# VFDClock.net
KiCad netlist of a schematic drawn in EAGLE
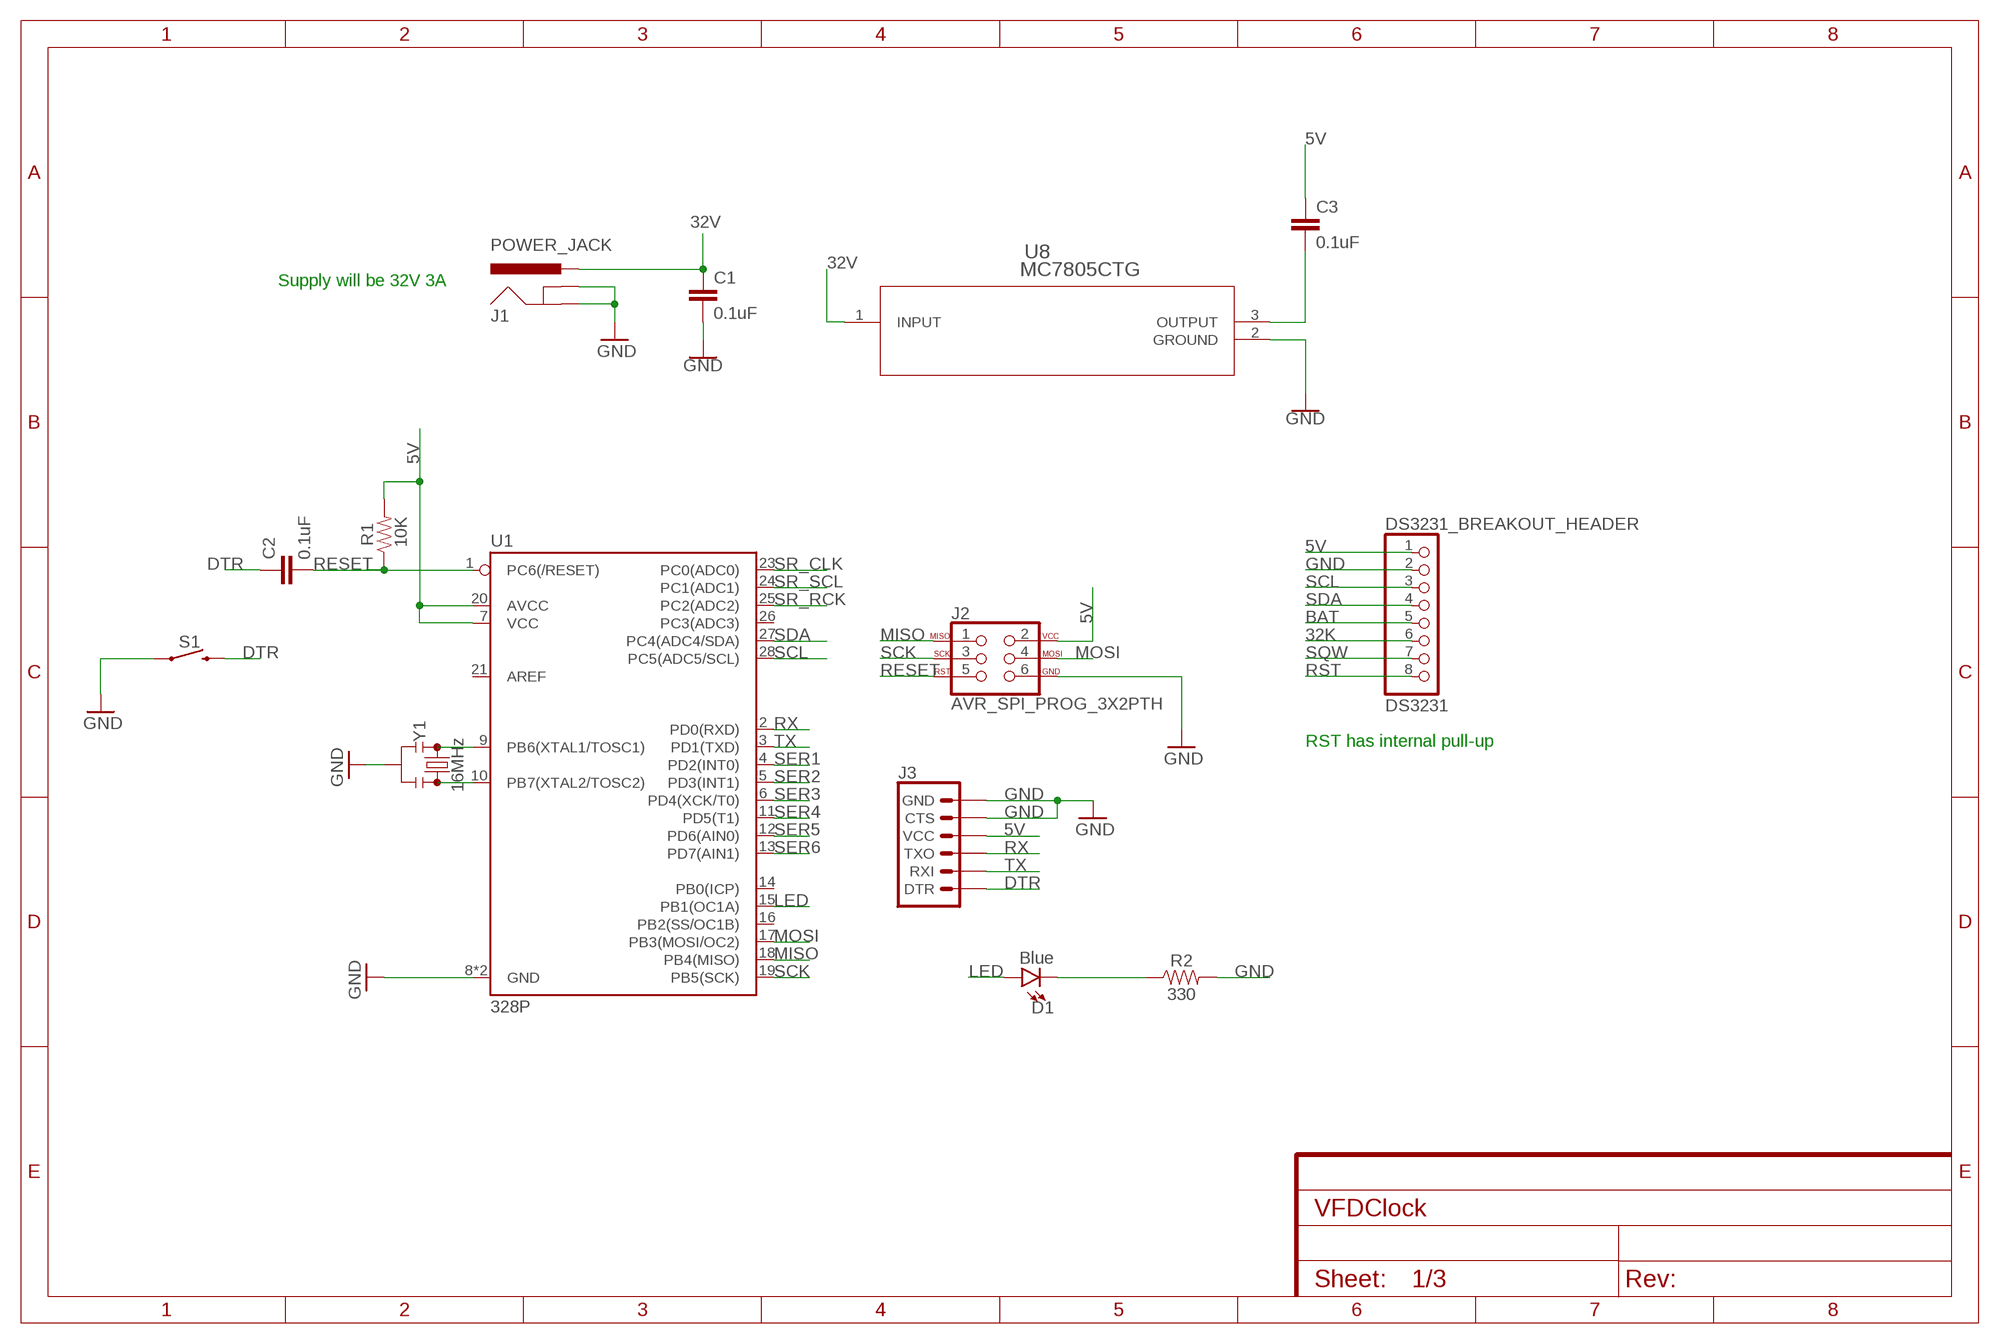
[diagram p0: schematic, sheet 1]
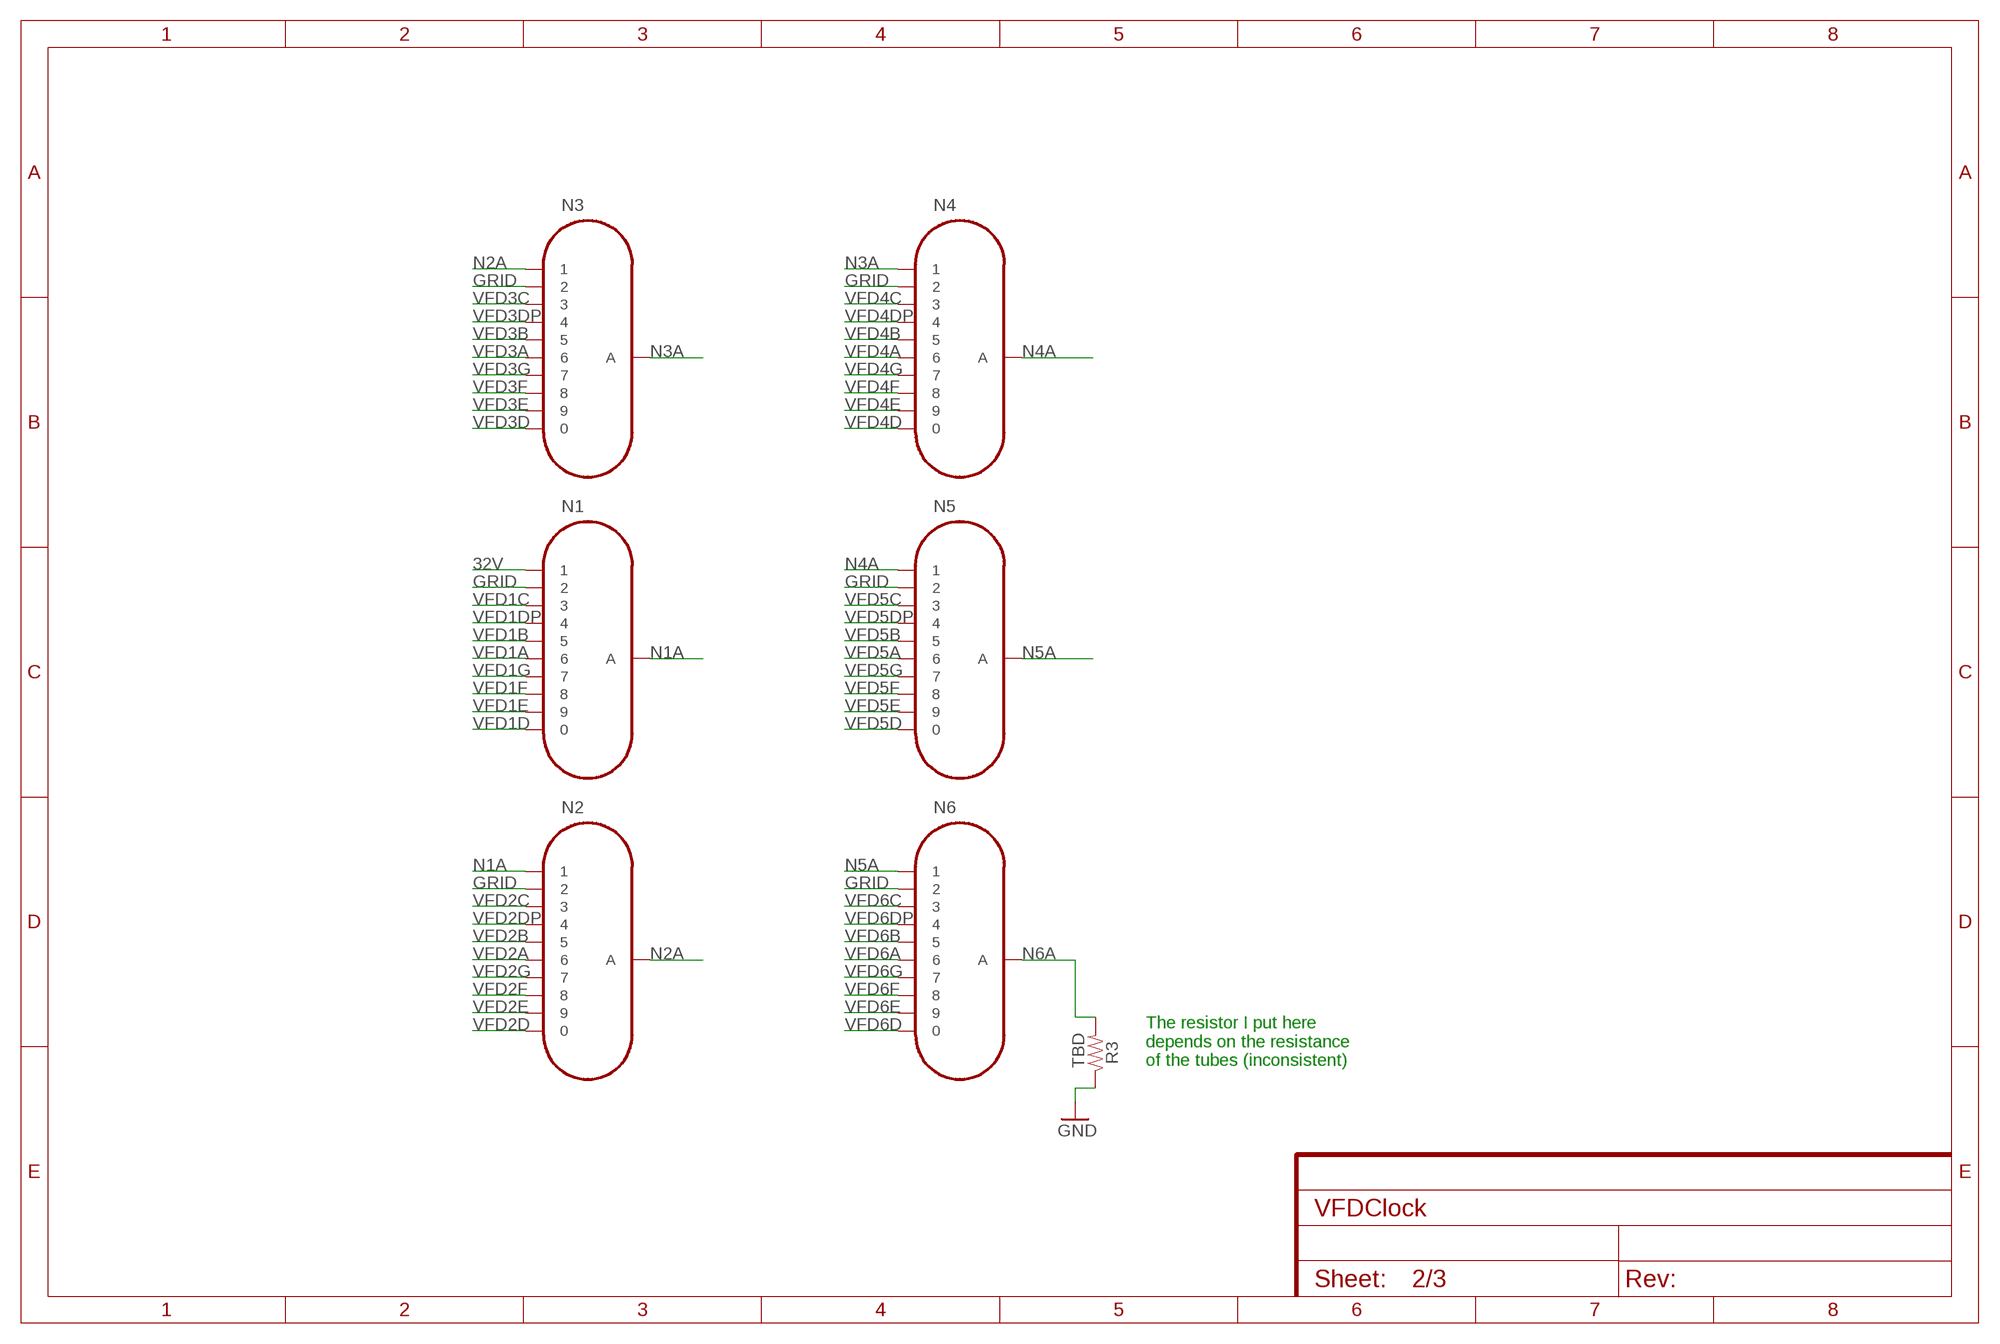
[diagram p1: schematic, sheet 2]
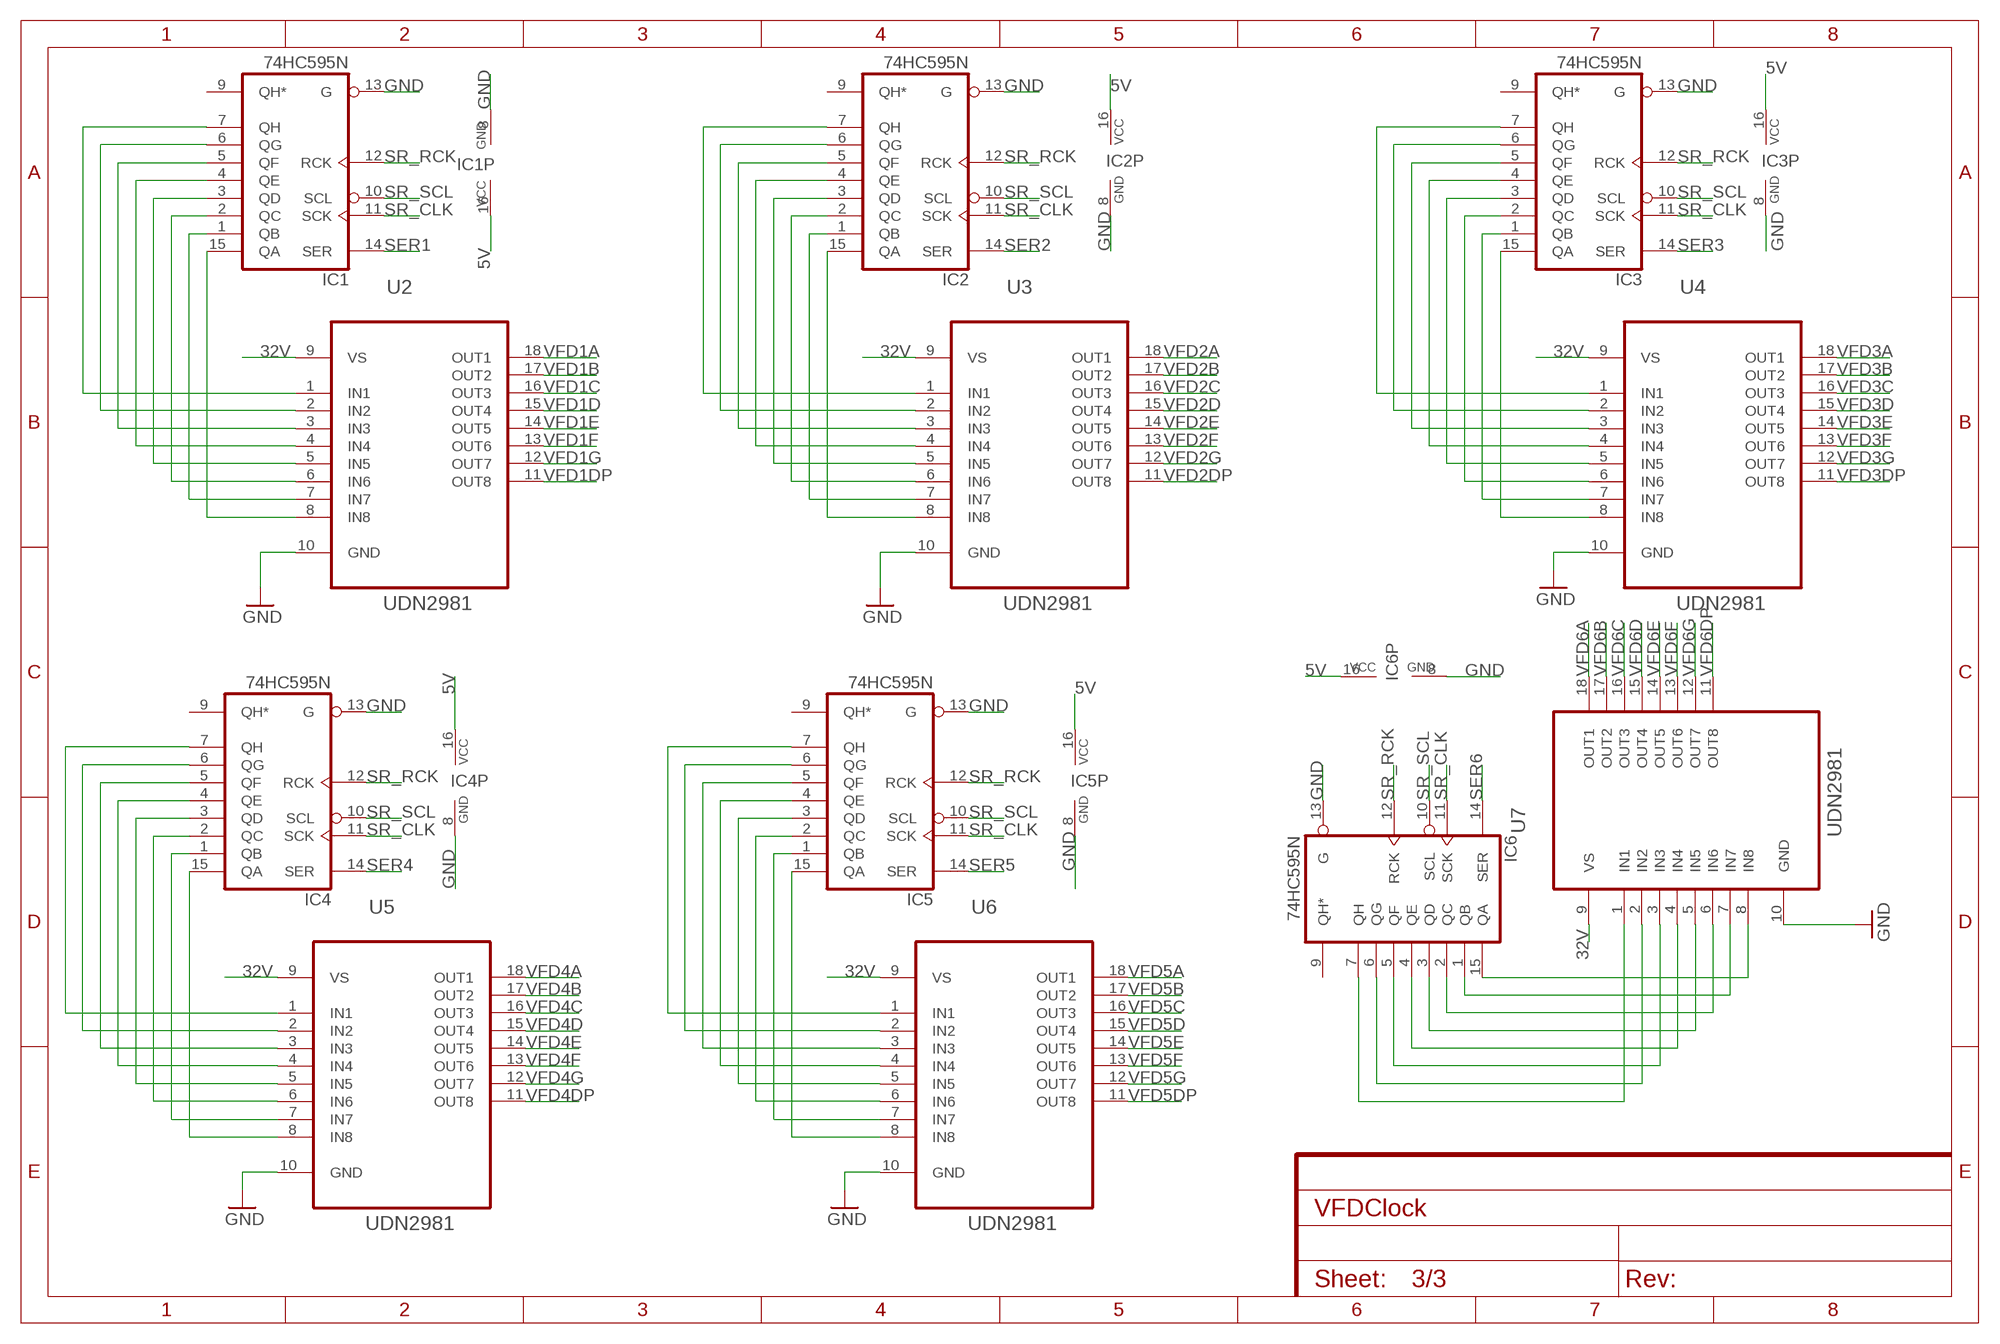
[diagram p2: schematic, sheet 3]

(export (version "E")
  (design (tool "Eeschema 10.0.6"))
  (components
    (comp (ref "C1")
      (value "0.1uF")
      (footprint "eagle-import:CAP-PTH-SMALL-KIT")
      (libsource (lib "eagle-import") (part "0.1UF-KIT-EZ-50V-20%"))
    )
    (comp (ref "C2")
      (value "0.1uF")
      (footprint "eagle-import:CAP-PTH-SMALL-KIT")
      (libsource (lib "eagle-import") (part "0.1UF-KIT-EZ-50V-20%"))
    )
    (comp (ref "C3")
      (value "0.1uF")
      (footprint "eagle-import:0402-CAP")
      (libsource (lib "eagle-import") (part ".1UF-CER"))
    )
    (comp (ref "D1")
      (value "Blue")
      (footprint "eagle-import:LED_5MM")
      (libsource (lib "eagle-import") (part "LED5MM"))
    )
    (comp (ref "DS3231_BREAKOUT_HEADER")
      (value "DS3231")
      (footprint "eagle-import:1X08_ROUND_70")
      (libsource (lib "eagle-import") (part "HEADER-1X870MIL"))
    )
    (comp (ref "J1")
      (value "POWER_JACK")
      (footprint "eagle-import:POWER_JACK_PTH")
      (libsource (lib "eagle-import") (part "POWER_JACK"))
    )
    (comp (ref "J2")
      (value "AVR_SPI_PROG_3X2PTH")
      (footprint "eagle-import:2X3")
      (libsource (lib "eagle-import") (part "AVR_SPI_PROG_3X2PTH"))
    )
    (comp (ref "J3")
      (value "6_PIN_SERIAL_TARGETLONGPADS")
      (footprint "eagle-import:1X06_LONGPADS")
      (libsource (lib "eagle-import") (part "6_PIN_SERIAL_TARGETLONGPADS"))
    )
    (comp (ref "R1")
      (value "10K")
      (footprint "eagle-import:AXIAL-0.3")
      (libsource (lib "eagle-import") (part "RESISTORAXIAL-0.3"))
    )
    (comp (ref "R2")
      (value "330")
      (footprint "eagle-import:AXIAL-0.3")
      (libsource (lib "eagle-import") (part "330OHM-HORIZ-1/10W-5%"))
    )
    (comp (ref "S1")
      (value "MOMENTARY-SWITCH-SPST-PTH-6.0MM")
      (footprint "eagle-import:TACTILE_SWITCH_PTH_6.0MM")
      (libsource (lib "eagle-import") (part "MOMENTARY-SWITCH-SPST-PTH-6.0MM"))
    )
    (comp (ref "U1")
      (value "328P")
      (footprint "eagle-import:DIP28")
      (libsource (lib "eagle-import") (part "ATMEGA328P_PDIP"))
    )
    (comp (ref "U8")
      (value "MC7805CTG")
      (footprint "eagle-import:TO-220AB")
      (libsource (lib "eagle-import") (part "MC7805CTG"))
    )
    (comp (ref "Y1")
      (value "16MHz")
      (footprint "eagle-import:RESONATOR-PTH-7.6X3.8")
      (libsource (lib "eagle-import") (part "RESONATORPTH-7.6X3.8"))
    )
    (comp (ref "N1")
      (value "IN-8")
      (footprint "eagle-import:IN-8")
      (libsource (lib "eagle-import") (part "IN-8"))
    )
    (comp (ref "N2")
      (value "IN-8")
      (footprint "eagle-import:IN-8")
      (libsource (lib "eagle-import") (part "IN-8"))
    )
    (comp (ref "N3")
      (value "IN-8")
      (footprint "eagle-import:IN-8")
      (libsource (lib "eagle-import") (part "IN-8"))
    )
    (comp (ref "N4")
      (value "IN-8")
      (footprint "eagle-import:IN-8")
      (libsource (lib "eagle-import") (part "IN-8"))
    )
    (comp (ref "N5")
      (value "IN-8")
      (footprint "eagle-import:IN-8")
      (libsource (lib "eagle-import") (part "IN-8"))
    )
    (comp (ref "N6")
      (value "IN-8")
      (footprint "eagle-import:IN-8")
      (libsource (lib "eagle-import") (part "IN-8"))
    )
    (comp (ref "R3")
      (value "TBD")
      (footprint "eagle-import:AXIAL-0.3")
      (libsource (lib "eagle-import") (part "RESISTORAXIAL-0.3"))
    )
    (comp (ref "IC1")
      (value "74HC595N")
      (footprint "eagle-import:DIL16")
      (libsource (lib "eagle-import") (part "74595NHC"))
    )
    (comp (ref "IC2")
      (value "74HC595N")
      (footprint "eagle-import:DIL16")
      (libsource (lib "eagle-import") (part "74595NHC"))
    )
    (comp (ref "IC3")
      (value "74HC595N")
      (footprint "eagle-import:DIL16")
      (libsource (lib "eagle-import") (part "74595NHC"))
    )
    (comp (ref "IC4")
      (value "74HC595N")
      (footprint "eagle-import:DIL16")
      (libsource (lib "eagle-import") (part "74595NHC"))
    )
    (comp (ref "IC5")
      (value "74HC595N")
      (footprint "eagle-import:DIL16")
      (libsource (lib "eagle-import") (part "74595NHC"))
    )
    (comp (ref "IC6")
      (value "74HC595N")
      (footprint "eagle-import:DIL16")
      (libsource (lib "eagle-import") (part "74595NHC"))
    )
    (comp (ref "U2")
      (value "UDN2981")
      (footprint "eagle-import:DIP254P762X533-18")
      (fields (field (name "MF") "Allegro MicroSystems LLC"))
      (libsource (lib "eagle-import") (part "UDN2981"))
    )
    (comp (ref "U3")
      (value "UDN2981")
      (footprint "eagle-import:DIP254P762X533-18")
      (fields (field (name "MF") "Allegro MicroSystems LLC"))
      (libsource (lib "eagle-import") (part "UDN2981"))
    )
    (comp (ref "U4")
      (value "UDN2981")
      (footprint "eagle-import:DIP254P762X533-18")
      (fields (field (name "MF") "Allegro MicroSystems LLC"))
      (libsource (lib "eagle-import") (part "UDN2981"))
    )
    (comp (ref "U5")
      (value "UDN2981")
      (footprint "eagle-import:DIP254P762X533-18")
      (fields (field (name "MF") "Allegro MicroSystems LLC"))
      (libsource (lib "eagle-import") (part "UDN2981"))
    )
    (comp (ref "U6")
      (value "UDN2981")
      (footprint "eagle-import:DIP254P762X533-18")
      (fields (field (name "MF") "Allegro MicroSystems LLC"))
      (libsource (lib "eagle-import") (part "UDN2981"))
    )
    (comp (ref "U7")
      (value "UDN2981")
      (footprint "eagle-import:DIP254P762X533-18")
      (fields (field (name "MF") "Allegro MicroSystems LLC"))
      (libsource (lib "eagle-import") (part "UDN2981"))
    )
  )
  (nets
    (net (code "1") (name "5V") (class "Default")
      (node (ref "C3") (pin "1") (pinfunction "1_1") (pintype "passive"))
      (node (ref "DS3231_BREAKOUT_HEADER") (pin "1") (pinfunction "1_1") (pintype "passive"))
      (node (ref "IC1") (pin "16") (pinfunction "VCC_16") (pintype "power_in"))
      (node (ref "IC2") (pin "16") (pinfunction "VCC_16") (pintype "power_in"))
      (node (ref "IC3") (pin "16") (pinfunction "VCC_16") (pintype "power_in"))
      (node (ref "IC4") (pin "16") (pinfunction "VCC_16") (pintype "power_in"))
      (node (ref "IC5") (pin "16") (pinfunction "VCC_16") (pintype "power_in"))
      (node (ref "IC6") (pin "16") (pinfunction "VCC_16") (pintype "power_in"))
      (node (ref "J2") (pin "2") (pinfunction "2_2") (pintype "passive"))
      (node (ref "J3") (pin "4") (pinfunction "VCC_4") (pintype "passive"))
      (node (ref "R1") (pin "P$2") (pinfunction "2_P$2") (pintype "passive"))
      (node (ref "U1") (pin "20") (pinfunction "AVCC_20") (pintype "bidirectional"))
      (node (ref "U1") (pin "7") (pinfunction "VCC_7") (pintype "bidirectional"))
    )
    (net (code "2") (name "32K") (class "Default")
      (node (ref "DS3231_BREAKOUT_HEADER") (pin "6") (pinfunction "6_6") (pintype "passive"))
    )
    (net (code "3") (name "32V") (class "Default")
      (node (ref "C1") (pin "1") (pinfunction "1_1") (pintype "passive"))
      (node (ref "J1") (pin "PWR") (pinfunction "PWR_PWR") (pintype "bidirectional"))
      (node (ref "N1") (pin "1") (pinfunction "1_1") (pintype "bidirectional"))
      (node (ref "U2") (pin "9") (pinfunction "VS_9") (pintype "power_in"))
      (node (ref "U3") (pin "9") (pinfunction "VS_9") (pintype "power_in"))
      (node (ref "U4") (pin "9") (pinfunction "VS_9") (pintype "power_in"))
      (node (ref "U5") (pin "9") (pinfunction "VS_9") (pintype "power_in"))
      (node (ref "U6") (pin "9") (pinfunction "VS_9") (pintype "power_in"))
      (node (ref "U7") (pin "9") (pinfunction "VS_9") (pintype "power_in"))
      (node (ref "U8") (pin "1") (pinfunction "INPUT_1") (pintype "input"))
    )
    (net (code "4") (name "BAT") (class "Default")
      (node (ref "DS3231_BREAKOUT_HEADER") (pin "5") (pinfunction "5_5") (pintype "passive"))
    )
    (net (code "5") (name "DTR") (class "Default")
      (node (ref "C2") (pin "1") (pinfunction "1_1") (pintype "passive"))
      (node (ref "J3") (pin "1") (pinfunction "DTR_1") (pintype "passive"))
      (node (ref "S1") (pin "3") (pinfunction "2_3") (pintype "passive"))
    )
    (net (code "6") (name "GND") (class "Default")
      (node (ref "C1") (pin "2") (pinfunction "2_2") (pintype "passive"))
      (node (ref "DS3231_BREAKOUT_HEADER") (pin "2") (pinfunction "2_2") (pintype "passive"))
      (node (ref "IC1") (pin "13") (pinfunction "G_13") (pintype "input"))
      (node (ref "IC1") (pin "8") (pinfunction "GND_8") (pintype "power_in"))
      (node (ref "IC2") (pin "13") (pinfunction "G_13") (pintype "input"))
      (node (ref "IC2") (pin "8") (pinfunction "GND_8") (pintype "power_in"))
      (node (ref "IC3") (pin "13") (pinfunction "G_13") (pintype "input"))
      (node (ref "IC3") (pin "8") (pinfunction "GND_8") (pintype "power_in"))
      (node (ref "IC4") (pin "13") (pinfunction "G_13") (pintype "input"))
      (node (ref "IC4") (pin "8") (pinfunction "GND_8") (pintype "power_in"))
      (node (ref "IC5") (pin "13") (pinfunction "G_13") (pintype "input"))
      (node (ref "IC5") (pin "8") (pinfunction "GND_8") (pintype "power_in"))
      (node (ref "IC6") (pin "13") (pinfunction "G_13") (pintype "input"))
      (node (ref "IC6") (pin "8") (pinfunction "GND_8") (pintype "power_in"))
      (node (ref "J1") (pin "GND") (pinfunction "GND_GND") (pintype "bidirectional"))
      (node (ref "J1") (pin "GNDBREAK") (pinfunction "GNDBREAK_GNDBREAK") (pintype "bidirectional"))
      (node (ref "J2") (pin "6") (pinfunction "6_6") (pintype "passive"))
      (node (ref "J3") (pin "5") (pinfunction "CTS_5") (pintype "passive"))
      (node (ref "J3") (pin "6") (pinfunction "GND_6") (pintype "passive"))
      (node (ref "R2") (pin "P$2") (pinfunction "2_P$2") (pintype "passive"))
      (node (ref "R3") (pin "P$1") (pinfunction "1_P$1") (pintype "passive"))
      (node (ref "S1") (pin "1") (pinfunction "1_1") (pintype "passive"))
      (node (ref "U1") (pin "22") (pinfunction "GND_22") (pintype "bidirectional"))
      (node (ref "U1") (pin "8") (pinfunction "GND_8") (pintype "bidirectional"))
      (node (ref "U2") (pin "10") (pinfunction "GND_10") (pintype "passive"))
      (node (ref "U3") (pin "10") (pinfunction "GND_10") (pintype "passive"))
      (node (ref "U4") (pin "10") (pinfunction "GND_10") (pintype "passive"))
      (node (ref "U5") (pin "10") (pinfunction "GND_10") (pintype "passive"))
      (node (ref "U6") (pin "10") (pinfunction "GND_10") (pintype "passive"))
      (node (ref "U7") (pin "10") (pinfunction "GND_10") (pintype "passive"))
      (node (ref "U8") (pin "2") (pinfunction "GROUND_2") (pintype "power_in"))
      (node (ref "Y1") (pin "2") (pinfunction "2_2") (pintype "passive"))
    )
    (net (code "7") (name "GRID") (class "Default")
      (node (ref "N1") (pin "2") (pinfunction "2_2") (pintype "bidirectional"))
      (node (ref "N2") (pin "2") (pinfunction "2_2") (pintype "bidirectional"))
      (node (ref "N3") (pin "2") (pinfunction "2_2") (pintype "bidirectional"))
      (node (ref "N4") (pin "2") (pinfunction "2_2") (pintype "bidirectional"))
      (node (ref "N5") (pin "2") (pinfunction "2_2") (pintype "bidirectional"))
      (node (ref "N6") (pin "2") (pinfunction "2_2") (pintype "bidirectional"))
    )
    (net (code "8") (name "LED") (class "Default")
      (node (ref "D1") (pin "A") (pinfunction "A_A") (pintype "passive"))
      (node (ref "U1") (pin "15") (pinfunction "PB1(OC1A)_15") (pintype "bidirectional"))
    )
    (net (code "9") (name "MISO") (class "Default")
      (node (ref "J2") (pin "1") (pinfunction "1_1") (pintype "passive"))
      (node (ref "U1") (pin "18") (pinfunction "PB4(MISO)_18") (pintype "bidirectional"))
    )
    (net (code "10") (name "MOSI") (class "Default")
      (node (ref "J2") (pin "4") (pinfunction "4_4") (pintype "passive"))
      (node (ref "U1") (pin "17") (pinfunction "PB3(MOSI/OC2)_17") (pintype "bidirectional"))
    )
    (net (code "11") (name "N1A") (class "Default")
      (node (ref "N1") (pin "A") (pinfunction "A_A") (pintype "bidirectional"))
      (node (ref "N2") (pin "1") (pinfunction "1_1") (pintype "bidirectional"))
    )
    (net (code "12") (name "N2A") (class "Default")
      (node (ref "N2") (pin "A") (pinfunction "A_A") (pintype "bidirectional"))
      (node (ref "N3") (pin "1") (pinfunction "1_1") (pintype "bidirectional"))
    )
    (net (code "13") (name "N3A") (class "Default")
      (node (ref "N3") (pin "A") (pinfunction "A_A") (pintype "bidirectional"))
      (node (ref "N4") (pin "1") (pinfunction "1_1") (pintype "bidirectional"))
    )
    (net (code "14") (name "N4A") (class "Default")
      (node (ref "N4") (pin "A") (pinfunction "A_A") (pintype "bidirectional"))
      (node (ref "N5") (pin "1") (pinfunction "1_1") (pintype "bidirectional"))
    )
    (net (code "15") (name "N5A") (class "Default")
      (node (ref "N5") (pin "A") (pinfunction "A_A") (pintype "bidirectional"))
      (node (ref "N6") (pin "1") (pinfunction "1_1") (pintype "bidirectional"))
    )
    (net (code "16") (name "N6A") (class "Default")
      (node (ref "N6") (pin "A") (pinfunction "A_A") (pintype "bidirectional"))
      (node (ref "R3") (pin "P$2") (pinfunction "2_P$2") (pintype "passive"))
    )
    (net (code "17") (name "Net-(D1-C)") (class "Default")
      (node (ref "D1") (pin "K") (pinfunction "C_K") (pintype "passive"))
      (node (ref "R2") (pin "P$1") (pinfunction "1_P$1") (pintype "passive"))
    )
    (net (code "18") (name "Net-(IC1A-QA)") (class "Default")
      (node (ref "IC1") (pin "15") (pinfunction "QA_15") (pintype "tri_state"))
      (node (ref "U2") (pin "8") (pinfunction "IN8_8") (pintype "input"))
    )
    (net (code "19") (name "Net-(IC1A-QB)") (class "Default")
      (node (ref "IC1") (pin "1") (pinfunction "QB_1") (pintype "tri_state"))
      (node (ref "U2") (pin "7") (pinfunction "IN7_7") (pintype "input"))
    )
    (net (code "20") (name "Net-(IC1A-QC)") (class "Default")
      (node (ref "IC1") (pin "2") (pinfunction "QC_2") (pintype "tri_state"))
      (node (ref "U2") (pin "6") (pinfunction "IN6_6") (pintype "input"))
    )
    (net (code "21") (name "Net-(IC1A-QD)") (class "Default")
      (node (ref "IC1") (pin "3") (pinfunction "QD_3") (pintype "tri_state"))
      (node (ref "U2") (pin "5") (pinfunction "IN5_5") (pintype "input"))
    )
    (net (code "22") (name "Net-(IC1A-QE)") (class "Default")
      (node (ref "IC1") (pin "4") (pinfunction "QE_4") (pintype "tri_state"))
      (node (ref "U2") (pin "4") (pinfunction "IN4_4") (pintype "input"))
    )
    (net (code "23") (name "Net-(IC1A-QF)") (class "Default")
      (node (ref "IC1") (pin "5") (pinfunction "QF_5") (pintype "tri_state"))
      (node (ref "U2") (pin "3") (pinfunction "IN3_3") (pintype "input"))
    )
    (net (code "24") (name "Net-(IC1A-QG)") (class "Default")
      (node (ref "IC1") (pin "6") (pinfunction "QG_6") (pintype "tri_state"))
      (node (ref "U2") (pin "2") (pinfunction "IN2_2") (pintype "input"))
    )
    (net (code "25") (name "Net-(IC1A-QH)") (class "Default")
      (node (ref "IC1") (pin "7") (pinfunction "QH_7") (pintype "tri_state"))
      (node (ref "U2") (pin "1") (pinfunction "IN1_1") (pintype "input"))
    )
    (net (code "26") (name "Net-(IC2A-QA)") (class "Default")
      (node (ref "IC2") (pin "15") (pinfunction "QA_15") (pintype "tri_state"))
      (node (ref "U3") (pin "8") (pinfunction "IN8_8") (pintype "input"))
    )
    (net (code "27") (name "Net-(IC2A-QB)") (class "Default")
      (node (ref "IC2") (pin "1") (pinfunction "QB_1") (pintype "tri_state"))
      (node (ref "U3") (pin "7") (pinfunction "IN7_7") (pintype "input"))
    )
    (net (code "28") (name "Net-(IC2A-QC)") (class "Default")
      (node (ref "IC2") (pin "2") (pinfunction "QC_2") (pintype "tri_state"))
      (node (ref "U3") (pin "6") (pinfunction "IN6_6") (pintype "input"))
    )
    (net (code "29") (name "Net-(IC2A-QD)") (class "Default")
      (node (ref "IC2") (pin "3") (pinfunction "QD_3") (pintype "tri_state"))
      (node (ref "U3") (pin "5") (pinfunction "IN5_5") (pintype "input"))
    )
    (net (code "30") (name "Net-(IC2A-QE)") (class "Default")
      (node (ref "IC2") (pin "4") (pinfunction "QE_4") (pintype "tri_state"))
      (node (ref "U3") (pin "4") (pinfunction "IN4_4") (pintype "input"))
    )
    (net (code "31") (name "Net-(IC2A-QF)") (class "Default")
      (node (ref "IC2") (pin "5") (pinfunction "QF_5") (pintype "tri_state"))
      (node (ref "U3") (pin "3") (pinfunction "IN3_3") (pintype "input"))
    )
    (net (code "32") (name "Net-(IC2A-QG)") (class "Default")
      (node (ref "IC2") (pin "6") (pinfunction "QG_6") (pintype "tri_state"))
      (node (ref "U3") (pin "2") (pinfunction "IN2_2") (pintype "input"))
    )
    (net (code "33") (name "Net-(IC2A-QH)") (class "Default")
      (node (ref "IC2") (pin "7") (pinfunction "QH_7") (pintype "tri_state"))
      (node (ref "U3") (pin "1") (pinfunction "IN1_1") (pintype "input"))
    )
    (net (code "34") (name "Net-(IC3A-QA)") (class "Default")
      (node (ref "IC3") (pin "15") (pinfunction "QA_15") (pintype "tri_state"))
      (node (ref "U4") (pin "8") (pinfunction "IN8_8") (pintype "input"))
    )
    (net (code "35") (name "Net-(IC3A-QB)") (class "Default")
      (node (ref "IC3") (pin "1") (pinfunction "QB_1") (pintype "tri_state"))
      (node (ref "U4") (pin "7") (pinfunction "IN7_7") (pintype "input"))
    )
    (net (code "36") (name "Net-(IC3A-QC)") (class "Default")
      (node (ref "IC3") (pin "2") (pinfunction "QC_2") (pintype "tri_state"))
      (node (ref "U4") (pin "6") (pinfunction "IN6_6") (pintype "input"))
    )
    (net (code "37") (name "Net-(IC3A-QD)") (class "Default")
      (node (ref "IC3") (pin "3") (pinfunction "QD_3") (pintype "tri_state"))
      (node (ref "U4") (pin "5") (pinfunction "IN5_5") (pintype "input"))
    )
    (net (code "38") (name "Net-(IC3A-QE)") (class "Default")
      (node (ref "IC3") (pin "4") (pinfunction "QE_4") (pintype "tri_state"))
      (node (ref "U4") (pin "4") (pinfunction "IN4_4") (pintype "input"))
    )
    (net (code "39") (name "Net-(IC3A-QF)") (class "Default")
      (node (ref "IC3") (pin "5") (pinfunction "QF_5") (pintype "tri_state"))
      (node (ref "U4") (pin "3") (pinfunction "IN3_3") (pintype "input"))
    )
    (net (code "40") (name "Net-(IC3A-QG)") (class "Default")
      (node (ref "IC3") (pin "6") (pinfunction "QG_6") (pintype "tri_state"))
      (node (ref "U4") (pin "2") (pinfunction "IN2_2") (pintype "input"))
    )
    (net (code "41") (name "Net-(IC3A-QH)") (class "Default")
      (node (ref "IC3") (pin "7") (pinfunction "QH_7") (pintype "tri_state"))
      (node (ref "U4") (pin "1") (pinfunction "IN1_1") (pintype "input"))
    )
    (net (code "42") (name "Net-(IC4A-QA)") (class "Default")
      (node (ref "IC4") (pin "15") (pinfunction "QA_15") (pintype "tri_state"))
      (node (ref "U5") (pin "8") (pinfunction "IN8_8") (pintype "input"))
    )
    (net (code "43") (name "Net-(IC4A-QB)") (class "Default")
      (node (ref "IC4") (pin "1") (pinfunction "QB_1") (pintype "tri_state"))
      (node (ref "U5") (pin "7") (pinfunction "IN7_7") (pintype "input"))
    )
    (net (code "44") (name "Net-(IC4A-QC)") (class "Default")
      (node (ref "IC4") (pin "2") (pinfunction "QC_2") (pintype "tri_state"))
      (node (ref "U5") (pin "6") (pinfunction "IN6_6") (pintype "input"))
    )
    (net (code "45") (name "Net-(IC4A-QD)") (class "Default")
      (node (ref "IC4") (pin "3") (pinfunction "QD_3") (pintype "tri_state"))
      (node (ref "U5") (pin "5") (pinfunction "IN5_5") (pintype "input"))
    )
    (net (code "46") (name "Net-(IC4A-QE)") (class "Default")
      (node (ref "IC4") (pin "4") (pinfunction "QE_4") (pintype "tri_state"))
      (node (ref "U5") (pin "4") (pinfunction "IN4_4") (pintype "input"))
    )
    (net (code "47") (name "Net-(IC4A-QF)") (class "Default")
      (node (ref "IC4") (pin "5") (pinfunction "QF_5") (pintype "tri_state"))
      (node (ref "U5") (pin "3") (pinfunction "IN3_3") (pintype "input"))
    )
    (net (code "48") (name "Net-(IC4A-QG)") (class "Default")
      (node (ref "IC4") (pin "6") (pinfunction "QG_6") (pintype "tri_state"))
      (node (ref "U5") (pin "2") (pinfunction "IN2_2") (pintype "input"))
    )
    (net (code "49") (name "Net-(IC4A-QH)") (class "Default")
      (node (ref "IC4") (pin "7") (pinfunction "QH_7") (pintype "tri_state"))
      (node (ref "U5") (pin "1") (pinfunction "IN1_1") (pintype "input"))
    )
    (net (code "50") (name "Net-(IC5A-QA)") (class "Default")
      (node (ref "IC5") (pin "15") (pinfunction "QA_15") (pintype "tri_state"))
      (node (ref "U6") (pin "8") (pinfunction "IN8_8") (pintype "input"))
    )
    (net (code "51") (name "Net-(IC5A-QB)") (class "Default")
      (node (ref "IC5") (pin "1") (pinfunction "QB_1") (pintype "tri_state"))
      (node (ref "U6") (pin "7") (pinfunction "IN7_7") (pintype "input"))
    )
    (net (code "52") (name "Net-(IC5A-QC)") (class "Default")
      (node (ref "IC5") (pin "2") (pinfunction "QC_2") (pintype "tri_state"))
      (node (ref "U6") (pin "6") (pinfunction "IN6_6") (pintype "input"))
    )
    (net (code "53") (name "Net-(IC5A-QD)") (class "Default")
      (node (ref "IC5") (pin "3") (pinfunction "QD_3") (pintype "tri_state"))
      (node (ref "U6") (pin "5") (pinfunction "IN5_5") (pintype "input"))
    )
    (net (code "54") (name "Net-(IC5A-QE)") (class "Default")
      (node (ref "IC5") (pin "4") (pinfunction "QE_4") (pintype "tri_state"))
      (node (ref "U6") (pin "4") (pinfunction "IN4_4") (pintype "input"))
    )
    (net (code "55") (name "Net-(IC5A-QF)") (class "Default")
      (node (ref "IC5") (pin "5") (pinfunction "QF_5") (pintype "tri_state"))
      (node (ref "U6") (pin "3") (pinfunction "IN3_3") (pintype "input"))
    )
    (net (code "56") (name "Net-(IC5A-QG)") (class "Default")
      (node (ref "IC5") (pin "6") (pinfunction "QG_6") (pintype "tri_state"))
      (node (ref "U6") (pin "2") (pinfunction "IN2_2") (pintype "input"))
    )
    (net (code "57") (name "Net-(IC5A-QH)") (class "Default")
      (node (ref "IC5") (pin "7") (pinfunction "QH_7") (pintype "tri_state"))
      (node (ref "U6") (pin "1") (pinfunction "IN1_1") (pintype "input"))
    )
    (net (code "58") (name "Net-(IC6A-QA)") (class "Default")
      (node (ref "IC6") (pin "15") (pinfunction "QA_15") (pintype "tri_state"))
      (node (ref "U7") (pin "8") (pinfunction "IN8_8") (pintype "input"))
    )
    (net (code "59") (name "Net-(IC6A-QB)") (class "Default")
      (node (ref "IC6") (pin "1") (pinfunction "QB_1") (pintype "tri_state"))
      (node (ref "U7") (pin "7") (pinfunction "IN7_7") (pintype "input"))
    )
    (net (code "60") (name "Net-(IC6A-QC)") (class "Default")
      (node (ref "IC6") (pin "2") (pinfunction "QC_2") (pintype "tri_state"))
      (node (ref "U7") (pin "6") (pinfunction "IN6_6") (pintype "input"))
    )
    (net (code "61") (name "Net-(IC6A-QD)") (class "Default")
      (node (ref "IC6") (pin "3") (pinfunction "QD_3") (pintype "tri_state"))
      (node (ref "U7") (pin "5") (pinfunction "IN5_5") (pintype "input"))
    )
    (net (code "62") (name "Net-(IC6A-QE)") (class "Default")
      (node (ref "IC6") (pin "4") (pinfunction "QE_4") (pintype "tri_state"))
      (node (ref "U7") (pin "4") (pinfunction "IN4_4") (pintype "input"))
    )
    (net (code "63") (name "Net-(IC6A-QF)") (class "Default")
      (node (ref "IC6") (pin "5") (pinfunction "QF_5") (pintype "tri_state"))
      (node (ref "U7") (pin "3") (pinfunction "IN3_3") (pintype "input"))
    )
    (net (code "64") (name "Net-(IC6A-QG)") (class "Default")
      (node (ref "IC6") (pin "6") (pinfunction "QG_6") (pintype "tri_state"))
      (node (ref "U7") (pin "2") (pinfunction "IN2_2") (pintype "input"))
    )
    (net (code "65") (name "Net-(IC6A-QH)") (class "Default")
      (node (ref "IC6") (pin "7") (pinfunction "QH_7") (pintype "tri_state"))
      (node (ref "U7") (pin "1") (pinfunction "IN1_1") (pintype "input"))
    )
    (net (code "66") (name "Net-(U1-PB6(XTAL1{slash}TOSC1))") (class "Default")
      (node (ref "U1") (pin "9") (pinfunction "PB6(XTAL1/TOSC1)_9") (pintype "bidirectional"))
      (node (ref "Y1") (pin "1") (pinfunction "1_1") (pintype "passive"))
    )
    (net (code "67") (name "Net-(U1-PB7(XTAL2{slash}TOSC2))") (class "Default")
      (node (ref "U1") (pin "10") (pinfunction "PB7(XTAL2/TOSC2)_10") (pintype "bidirectional"))
      (node (ref "Y1") (pin "3") (pinfunction "3_3") (pintype "passive"))
    )
    (net (code "68") (name "Net-(U8-OUTPUT)") (class "Default")
      (node (ref "C3") (pin "2") (pinfunction "2_2") (pintype "passive"))
      (node (ref "U8") (pin "3") (pinfunction "OUTPUT_3") (pintype "output"))
    )
    (net (code "69") (name "RESET") (class "Default")
      (node (ref "C2") (pin "2") (pinfunction "2_2") (pintype "passive"))
      (node (ref "J2") (pin "5") (pinfunction "5_5") (pintype "passive"))
      (node (ref "R1") (pin "P$1") (pinfunction "1_P$1") (pintype "passive"))
      (node (ref "U1") (pin "1") (pinfunction "PC6(/RESET)_1") (pintype "bidirectional"))
    )
    (net (code "70") (name "RST") (class "Default")
      (node (ref "DS3231_BREAKOUT_HEADER") (pin "8") (pinfunction "8_8") (pintype "passive"))
    )
    (net (code "71") (name "RX") (class "Default")
      (node (ref "J3") (pin "3") (pinfunction "TXO_3") (pintype "passive"))
      (node (ref "U1") (pin "2") (pinfunction "PD0(RXD)_2") (pintype "bidirectional"))
    )
    (net (code "72") (name "SCK") (class "Default")
      (node (ref "J2") (pin "3") (pinfunction "3_3") (pintype "passive"))
      (node (ref "U1") (pin "19") (pinfunction "PB5(SCK)_19") (pintype "bidirectional"))
    )
    (net (code "73") (name "SCL") (class "Default")
      (node (ref "DS3231_BREAKOUT_HEADER") (pin "3") (pinfunction "3_3") (pintype "passive"))
      (node (ref "U1") (pin "28") (pinfunction "PC5(ADC5/SCL)_28") (pintype "bidirectional"))
    )
    (net (code "74") (name "SDA") (class "Default")
      (node (ref "DS3231_BREAKOUT_HEADER") (pin "4") (pinfunction "4_4") (pintype "passive"))
      (node (ref "U1") (pin "27") (pinfunction "PC4(ADC4/SDA)_27") (pintype "bidirectional"))
    )
    (net (code "75") (name "SER1") (class "Default")
      (node (ref "IC1") (pin "14") (pinfunction "SER_14") (pintype "input"))
      (node (ref "U1") (pin "4") (pinfunction "PD2(INT0)_4") (pintype "bidirectional"))
    )
    (net (code "76") (name "SER2") (class "Default")
      (node (ref "IC2") (pin "14") (pinfunction "SER_14") (pintype "input"))
      (node (ref "U1") (pin "5") (pinfunction "PD3(INT1)_5") (pintype "bidirectional"))
    )
    (net (code "77") (name "SER3") (class "Default")
      (node (ref "IC3") (pin "14") (pinfunction "SER_14") (pintype "input"))
      (node (ref "U1") (pin "6") (pinfunction "PD4(XCK/T0)_6") (pintype "bidirectional"))
    )
    (net (code "78") (name "SER4") (class "Default")
      (node (ref "IC4") (pin "14") (pinfunction "SER_14") (pintype "input"))
      (node (ref "U1") (pin "11") (pinfunction "PD5(T1)_11") (pintype "bidirectional"))
    )
    (net (code "79") (name "SER5") (class "Default")
      (node (ref "IC5") (pin "14") (pinfunction "SER_14") (pintype "input"))
      (node (ref "U1") (pin "12") (pinfunction "PD6(AIN0)_12") (pintype "bidirectional"))
    )
    (net (code "80") (name "SER6") (class "Default")
      (node (ref "IC6") (pin "14") (pinfunction "SER_14") (pintype "input"))
      (node (ref "U1") (pin "13") (pinfunction "PD7(AIN1)_13") (pintype "bidirectional"))
    )
    (net (code "81") (name "SQW") (class "Default")
      (node (ref "DS3231_BREAKOUT_HEADER") (pin "7") (pinfunction "7_7") (pintype "passive"))
    )
    (net (code "82") (name "SR_CLK") (class "Default")
      (node (ref "IC1") (pin "11") (pinfunction "SCK_11") (pintype "input"))
      (node (ref "IC2") (pin "11") (pinfunction "SCK_11") (pintype "input"))
      (node (ref "IC3") (pin "11") (pinfunction "SCK_11") (pintype "input"))
      (node (ref "IC4") (pin "11") (pinfunction "SCK_11") (pintype "input"))
      (node (ref "IC5") (pin "11") (pinfunction "SCK_11") (pintype "input"))
      (node (ref "IC6") (pin "11") (pinfunction "SCK_11") (pintype "input"))
      (node (ref "U1") (pin "23") (pinfunction "PC0(ADC0)_23") (pintype "bidirectional"))
    )
    (net (code "83") (name "SR_RCK") (class "Default")
      (node (ref "IC1") (pin "12") (pinfunction "RCK_12") (pintype "input"))
      (node (ref "IC2") (pin "12") (pinfunction "RCK_12") (pintype "input"))
      (node (ref "IC3") (pin "12") (pinfunction "RCK_12") (pintype "input"))
      (node (ref "IC4") (pin "12") (pinfunction "RCK_12") (pintype "input"))
      (node (ref "IC5") (pin "12") (pinfunction "RCK_12") (pintype "input"))
      (node (ref "IC6") (pin "12") (pinfunction "RCK_12") (pintype "input"))
      (node (ref "U1") (pin "25") (pinfunction "PC2(ADC2)_25") (pintype "bidirectional"))
    )
    (net (code "84") (name "SR_SCL") (class "Default")
      (node (ref "IC1") (pin "10") (pinfunction "SCL_10") (pintype "input"))
      (node (ref "IC2") (pin "10") (pinfunction "SCL_10") (pintype "input"))
      (node (ref "IC3") (pin "10") (pinfunction "SCL_10") (pintype "input"))
      (node (ref "IC4") (pin "10") (pinfunction "SCL_10") (pintype "input"))
      (node (ref "IC5") (pin "10") (pinfunction "SCL_10") (pintype "input"))
      (node (ref "IC6") (pin "10") (pinfunction "SCL_10") (pintype "input"))
      (node (ref "U1") (pin "24") (pinfunction "PC1(ADC1)_24") (pintype "bidirectional"))
    )
    (net (code "85") (name "TX") (class "Default")
      (node (ref "J3") (pin "2") (pinfunction "RXI_2") (pintype "passive"))
      (node (ref "U1") (pin "3") (pinfunction "PD1(TXD)_3") (pintype "bidirectional"))
    )
    (net (code "86") (name "VFD1A") (class "Default")
      (node (ref "N1") (pin "6") (pinfunction "6_6") (pintype "bidirectional"))
      (node (ref "U2") (pin "18") (pinfunction "OUT1_18") (pintype "output"))
    )
    (net (code "87") (name "VFD1B") (class "Default")
      (node (ref "N1") (pin "5") (pinfunction "5_5") (pintype "bidirectional"))
      (node (ref "U2") (pin "17") (pinfunction "OUT2_17") (pintype "output"))
    )
    (net (code "88") (name "VFD1C") (class "Default")
      (node (ref "N1") (pin "3") (pinfunction "3_3") (pintype "bidirectional"))
      (node (ref "U2") (pin "16") (pinfunction "OUT3_16") (pintype "output"))
    )
    (net (code "89") (name "VFD1D") (class "Default")
      (node (ref "N1") (pin "0") (pinfunction "0_0") (pintype "bidirectional"))
      (node (ref "U2") (pin "15") (pinfunction "OUT4_15") (pintype "output"))
    )
    (net (code "90") (name "VFD1DP") (class "Default")
      (node (ref "N1") (pin "4") (pinfunction "4_4") (pintype "bidirectional"))
      (node (ref "U2") (pin "11") (pinfunction "OUT8_11") (pintype "output"))
    )
    (net (code "91") (name "VFD1E") (class "Default")
      (node (ref "N1") (pin "9") (pinfunction "9_9") (pintype "bidirectional"))
      (node (ref "U2") (pin "14") (pinfunction "OUT5_14") (pintype "output"))
    )
    (net (code "92") (name "VFD1F") (class "Default")
      (node (ref "N1") (pin "8") (pinfunction "8_8") (pintype "bidirectional"))
      (node (ref "U2") (pin "13") (pinfunction "OUT6_13") (pintype "output"))
    )
    (net (code "93") (name "VFD1G") (class "Default")
      (node (ref "N1") (pin "7") (pinfunction "7_7") (pintype "bidirectional"))
      (node (ref "U2") (pin "12") (pinfunction "OUT7_12") (pintype "output"))
    )
    (net (code "94") (name "VFD2A") (class "Default")
      (node (ref "N2") (pin "6") (pinfunction "6_6") (pintype "bidirectional"))
      (node (ref "U3") (pin "18") (pinfunction "OUT1_18") (pintype "output"))
    )
    (net (code "95") (name "VFD2B") (class "Default")
      (node (ref "N2") (pin "5") (pinfunction "5_5") (pintype "bidirectional"))
      (node (ref "U3") (pin "17") (pinfunction "OUT2_17") (pintype "output"))
    )
    (net (code "96") (name "VFD2C") (class "Default")
      (node (ref "N2") (pin "3") (pinfunction "3_3") (pintype "bidirectional"))
      (node (ref "U3") (pin "16") (pinfunction "OUT3_16") (pintype "output"))
    )
    (net (code "97") (name "VFD2D") (class "Default")
      (node (ref "N2") (pin "0") (pinfunction "0_0") (pintype "bidirectional"))
      (node (ref "U3") (pin "15") (pinfunction "OUT4_15") (pintype "output"))
    )
    (net (code "98") (name "VFD2DP") (class "Default")
      (node (ref "N2") (pin "4") (pinfunction "4_4") (pintype "bidirectional"))
      (node (ref "U3") (pin "11") (pinfunction "OUT8_11") (pintype "output"))
    )
    (net (code "99") (name "VFD2E") (class "Default")
      (node (ref "N2") (pin "9") (pinfunction "9_9") (pintype "bidirectional"))
      (node (ref "U3") (pin "14") (pinfunction "OUT5_14") (pintype "output"))
    )
    (net (code "100") (name "VFD2F") (class "Default")
      (node (ref "N2") (pin "8") (pinfunction "8_8") (pintype "bidirectional"))
      (node (ref "U3") (pin "13") (pinfunction "OUT6_13") (pintype "output"))
    )
    (net (code "101") (name "VFD2G") (class "Default")
      (node (ref "N2") (pin "7") (pinfunction "7_7") (pintype "bidirectional"))
      (node (ref "U3") (pin "12") (pinfunction "OUT7_12") (pintype "output"))
    )
    (net (code "102") (name "VFD3A") (class "Default")
      (node (ref "N3") (pin "6") (pinfunction "6_6") (pintype "bidirectional"))
      (node (ref "U4") (pin "18") (pinfunction "OUT1_18") (pintype "output"))
    )
    (net (code "103") (name "VFD3B") (class "Default")
      (node (ref "N3") (pin "5") (pinfunction "5_5") (pintype "bidirectional"))
      (node (ref "U4") (pin "17") (pinfunction "OUT2_17") (pintype "output"))
    )
    (net (code "104") (name "VFD3C") (class "Default")
      (node (ref "N3") (pin "3") (pinfunction "3_3") (pintype "bidirectional"))
      (node (ref "U4") (pin "16") (pinfunction "OUT3_16") (pintype "output"))
    )
    (net (code "105") (name "VFD3D") (class "Default")
      (node (ref "N3") (pin "0") (pinfunction "0_0") (pintype "bidirectional"))
      (node (ref "U4") (pin "15") (pinfunction "OUT4_15") (pintype "output"))
    )
    (net (code "106") (name "VFD3DP") (class "Default")
      (node (ref "N3") (pin "4") (pinfunction "4_4") (pintype "bidirectional"))
      (node (ref "U4") (pin "11") (pinfunction "OUT8_11") (pintype "output"))
    )
    (net (code "107") (name "VFD3E") (class "Default")
      (node (ref "N3") (pin "9") (pinfunction "9_9") (pintype "bidirectional"))
      (node (ref "U4") (pin "14") (pinfunction "OUT5_14") (pintype "output"))
    )
    (net (code "108") (name "VFD3F") (class "Default")
      (node (ref "N3") (pin "8") (pinfunction "8_8") (pintype "bidirectional"))
      (node (ref "U4") (pin "13") (pinfunction "OUT6_13") (pintype "output"))
    )
    (net (code "109") (name "VFD3G") (class "Default")
      (node (ref "N3") (pin "7") (pinfunction "7_7") (pintype "bidirectional"))
      (node (ref "U4") (pin "12") (pinfunction "OUT7_12") (pintype "output"))
    )
    (net (code "110") (name "VFD4A") (class "Default")
      (node (ref "N4") (pin "6") (pinfunction "6_6") (pintype "bidirectional"))
      (node (ref "U5") (pin "18") (pinfunction "OUT1_18") (pintype "output"))
    )
    (net (code "111") (name "VFD4B") (class "Default")
      (node (ref "N4") (pin "5") (pinfunction "5_5") (pintype "bidirectional"))
      (node (ref "U5") (pin "17") (pinfunction "OUT2_17") (pintype "output"))
    )
    (net (code "112") (name "VFD4C") (class "Default")
      (node (ref "N4") (pin "3") (pinfunction "3_3") (pintype "bidirectional"))
      (node (ref "U5") (pin "16") (pinfunction "OUT3_16") (pintype "output"))
    )
    (net (code "113") (name "VFD4D") (class "Default")
      (node (ref "N4") (pin "0") (pinfunction "0_0") (pintype "bidirectional"))
      (node (ref "U5") (pin "15") (pinfunction "OUT4_15") (pintype "output"))
    )
    (net (code "114") (name "VFD4DP") (class "Default")
      (node (ref "N4") (pin "4") (pinfunction "4_4") (pintype "bidirectional"))
      (node (ref "U5") (pin "11") (pinfunction "OUT8_11") (pintype "output"))
    )
    (net (code "115") (name "VFD4E") (class "Default")
      (node (ref "N4") (pin "9") (pinfunction "9_9") (pintype "bidirectional"))
      (node (ref "U5") (pin "14") (pinfunction "OUT5_14") (pintype "output"))
    )
    (net (code "116") (name "VFD4F") (class "Default")
      (node (ref "N4") (pin "8") (pinfunction "8_8") (pintype "bidirectional"))
      (node (ref "U5") (pin "13") (pinfunction "OUT6_13") (pintype "output"))
    )
    (net (code "117") (name "VFD4G") (class "Default")
      (node (ref "N4") (pin "7") (pinfunction "7_7") (pintype "bidirectional"))
      (node (ref "U5") (pin "12") (pinfunction "OUT7_12") (pintype "output"))
    )
    (net (code "118") (name "VFD5A") (class "Default")
      (node (ref "N5") (pin "6") (pinfunction "6_6") (pintype "bidirectional"))
      (node (ref "U6") (pin "18") (pinfunction "OUT1_18") (pintype "output"))
    )
    (net (code "119") (name "VFD5B") (class "Default")
      (node (ref "N5") (pin "5") (pinfunction "5_5") (pintype "bidirectional"))
      (node (ref "U6") (pin "17") (pinfunction "OUT2_17") (pintype "output"))
    )
    (net (code "120") (name "VFD5C") (class "Default")
      (node (ref "N5") (pin "3") (pinfunction "3_3") (pintype "bidirectional"))
      (node (ref "U6") (pin "16") (pinfunction "OUT3_16") (pintype "output"))
    )
    (net (code "121") (name "VFD5D") (class "Default")
      (node (ref "N5") (pin "0") (pinfunction "0_0") (pintype "bidirectional"))
      (node (ref "U6") (pin "15") (pinfunction "OUT4_15") (pintype "output"))
    )
    (net (code "122") (name "VFD5DP") (class "Default")
      (node (ref "N5") (pin "4") (pinfunction "4_4") (pintype "bidirectional"))
      (node (ref "U6") (pin "11") (pinfunction "OUT8_11") (pintype "output"))
    )
    (net (code "123") (name "VFD5E") (class "Default")
      (node (ref "N5") (pin "9") (pinfunction "9_9") (pintype "bidirectional"))
      (node (ref "U6") (pin "14") (pinfunction "OUT5_14") (pintype "output"))
    )
    (net (code "124") (name "VFD5F") (class "Default")
      (node (ref "N5") (pin "8") (pinfunction "8_8") (pintype "bidirectional"))
      (node (ref "U6") (pin "13") (pinfunction "OUT6_13") (pintype "output"))
    )
    (net (code "125") (name "VFD5G") (class "Default")
      (node (ref "N5") (pin "7") (pinfunction "7_7") (pintype "bidirectional"))
      (node (ref "U6") (pin "12") (pinfunction "OUT7_12") (pintype "output"))
    )
    (net (code "126") (name "VFD6A") (class "Default")
      (node (ref "N6") (pin "6") (pinfunction "6_6") (pintype "bidirectional"))
      (node (ref "U7") (pin "18") (pinfunction "OUT1_18") (pintype "output"))
    )
    (net (code "127") (name "VFD6B") (class "Default")
      (node (ref "N6") (pin "5") (pinfunction "5_5") (pintype "bidirectional"))
      (node (ref "U7") (pin "17") (pinfunction "OUT2_17") (pintype "output"))
    )
    (net (code "128") (name "VFD6C") (class "Default")
      (node (ref "N6") (pin "3") (pinfunction "3_3") (pintype "bidirectional"))
      (node (ref "U7") (pin "16") (pinfunction "OUT3_16") (pintype "output"))
    )
    (net (code "129") (name "VFD6D") (class "Default")
      (node (ref "N6") (pin "0") (pinfunction "0_0") (pintype "bidirectional"))
      (node (ref "U7") (pin "15") (pinfunction "OUT4_15") (pintype "output"))
    )
    (net (code "130") (name "VFD6DP") (class "Default")
      (node (ref "N6") (pin "4") (pinfunction "4_4") (pintype "bidirectional"))
      (node (ref "U7") (pin "11") (pinfunction "OUT8_11") (pintype "output"))
    )
    (net (code "131") (name "VFD6E") (class "Default")
      (node (ref "N6") (pin "9") (pinfunction "9_9") (pintype "bidirectional"))
      (node (ref "U7") (pin "14") (pinfunction "OUT5_14") (pintype "output"))
    )
    (net (code "132") (name "VFD6F") (class "Default")
      (node (ref "N6") (pin "8") (pinfunction "8_8") (pintype "bidirectional"))
      (node (ref "U7") (pin "13") (pinfunction "OUT6_13") (pintype "output"))
    )
    (net (code "133") (name "VFD6G") (class "Default")
      (node (ref "N6") (pin "7") (pinfunction "7_7") (pintype "bidirectional"))
      (node (ref "U7") (pin "12") (pinfunction "OUT7_12") (pintype "output"))
    )
    (net (code "134") (name "unconnected-(IC1A-QH*-Pad9)") (class "Default")
      (node (ref "IC1") (pin "9") (pinfunction "QH*_9") (pintype "tri_state"))
    )
    (net (code "135") (name "unconnected-(IC2A-QH*-Pad9)") (class "Default")
      (node (ref "IC2") (pin "9") (pinfunction "QH*_9") (pintype "tri_state"))
    )
    (net (code "136") (name "unconnected-(IC3A-QH*-Pad9)") (class "Default")
      (node (ref "IC3") (pin "9") (pinfunction "QH*_9") (pintype "tri_state"))
    )
    (net (code "137") (name "unconnected-(IC4A-QH*-Pad9)") (class "Default")
      (node (ref "IC4") (pin "9") (pinfunction "QH*_9") (pintype "tri_state"))
    )
    (net (code "138") (name "unconnected-(IC5A-QH*-Pad9)") (class "Default")
      (node (ref "IC5") (pin "9") (pinfunction "QH*_9") (pintype "tri_state"))
    )
    (net (code "139") (name "unconnected-(IC6A-QH*-Pad9)") (class "Default")
      (node (ref "IC6") (pin "9") (pinfunction "QH*_9") (pintype "tri_state"))
    )
    (net (code "140") (name "unconnected-(U1-AREF-Pad21)") (class "Default")
      (node (ref "U1") (pin "21") (pinfunction "AREF_21") (pintype "bidirectional"))
    )
    (net (code "141") (name "unconnected-(U1-PB0(ICP)-Pad14)") (class "Default")
      (node (ref "U1") (pin "14") (pinfunction "PB0(ICP)_14") (pintype "bidirectional"))
    )
    (net (code "142") (name "unconnected-(U1-PB2(SS{slash}OC1B)-Pad16)") (class "Default")
      (node (ref "U1") (pin "16") (pinfunction "PB2(SS/OC1B)_16") (pintype "bidirectional"))
    )
    (net (code "143") (name "unconnected-(U1-PC3(ADC3)-Pad26)") (class "Default")
      (node (ref "U1") (pin "26") (pinfunction "PC3(ADC3)_26") (pintype "bidirectional"))
    )
  )
)
